# mippe_32u4.net
KiCad netlist of a schematic drawn in EAGLE
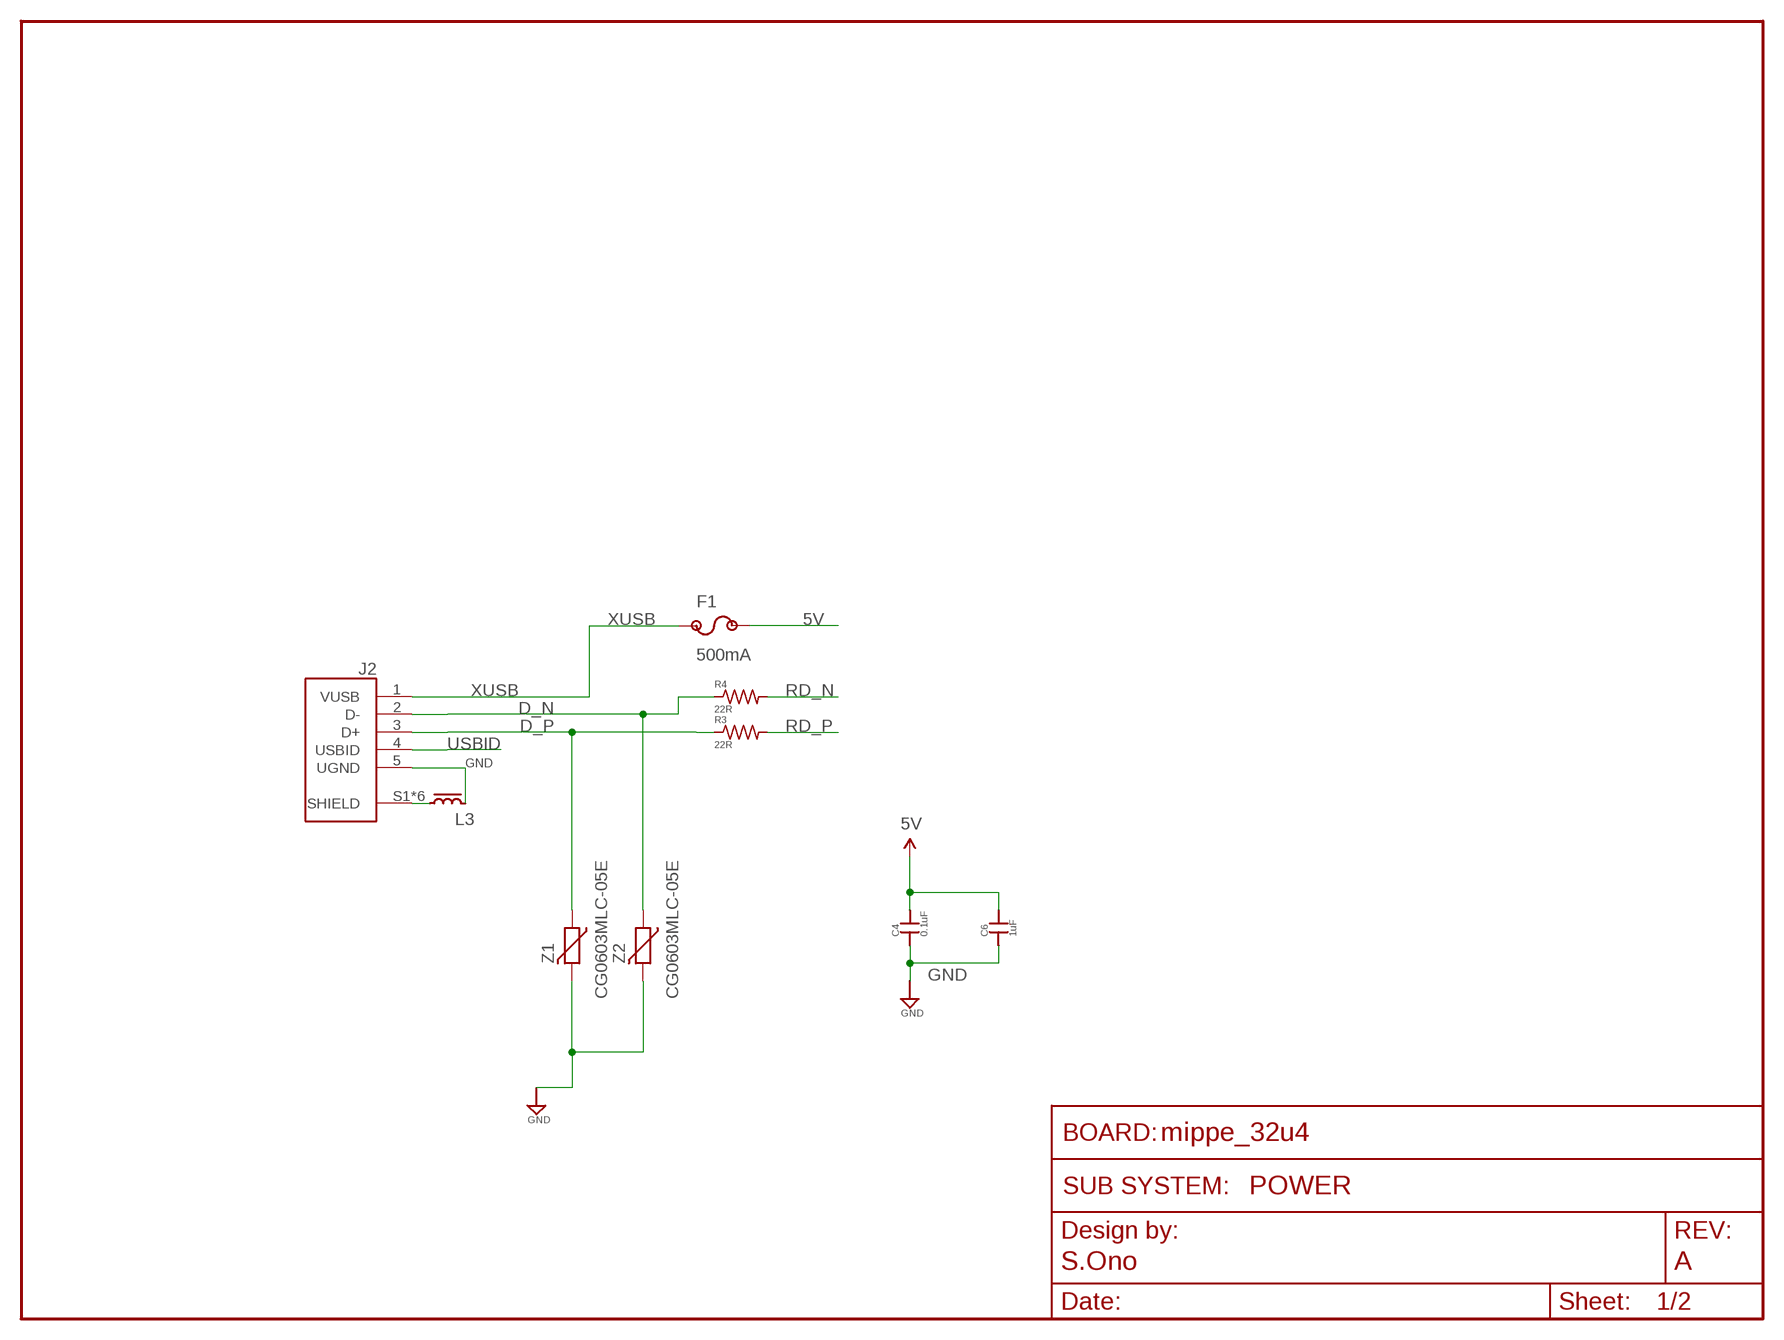
[diagram p0: schematic, sheet 1]
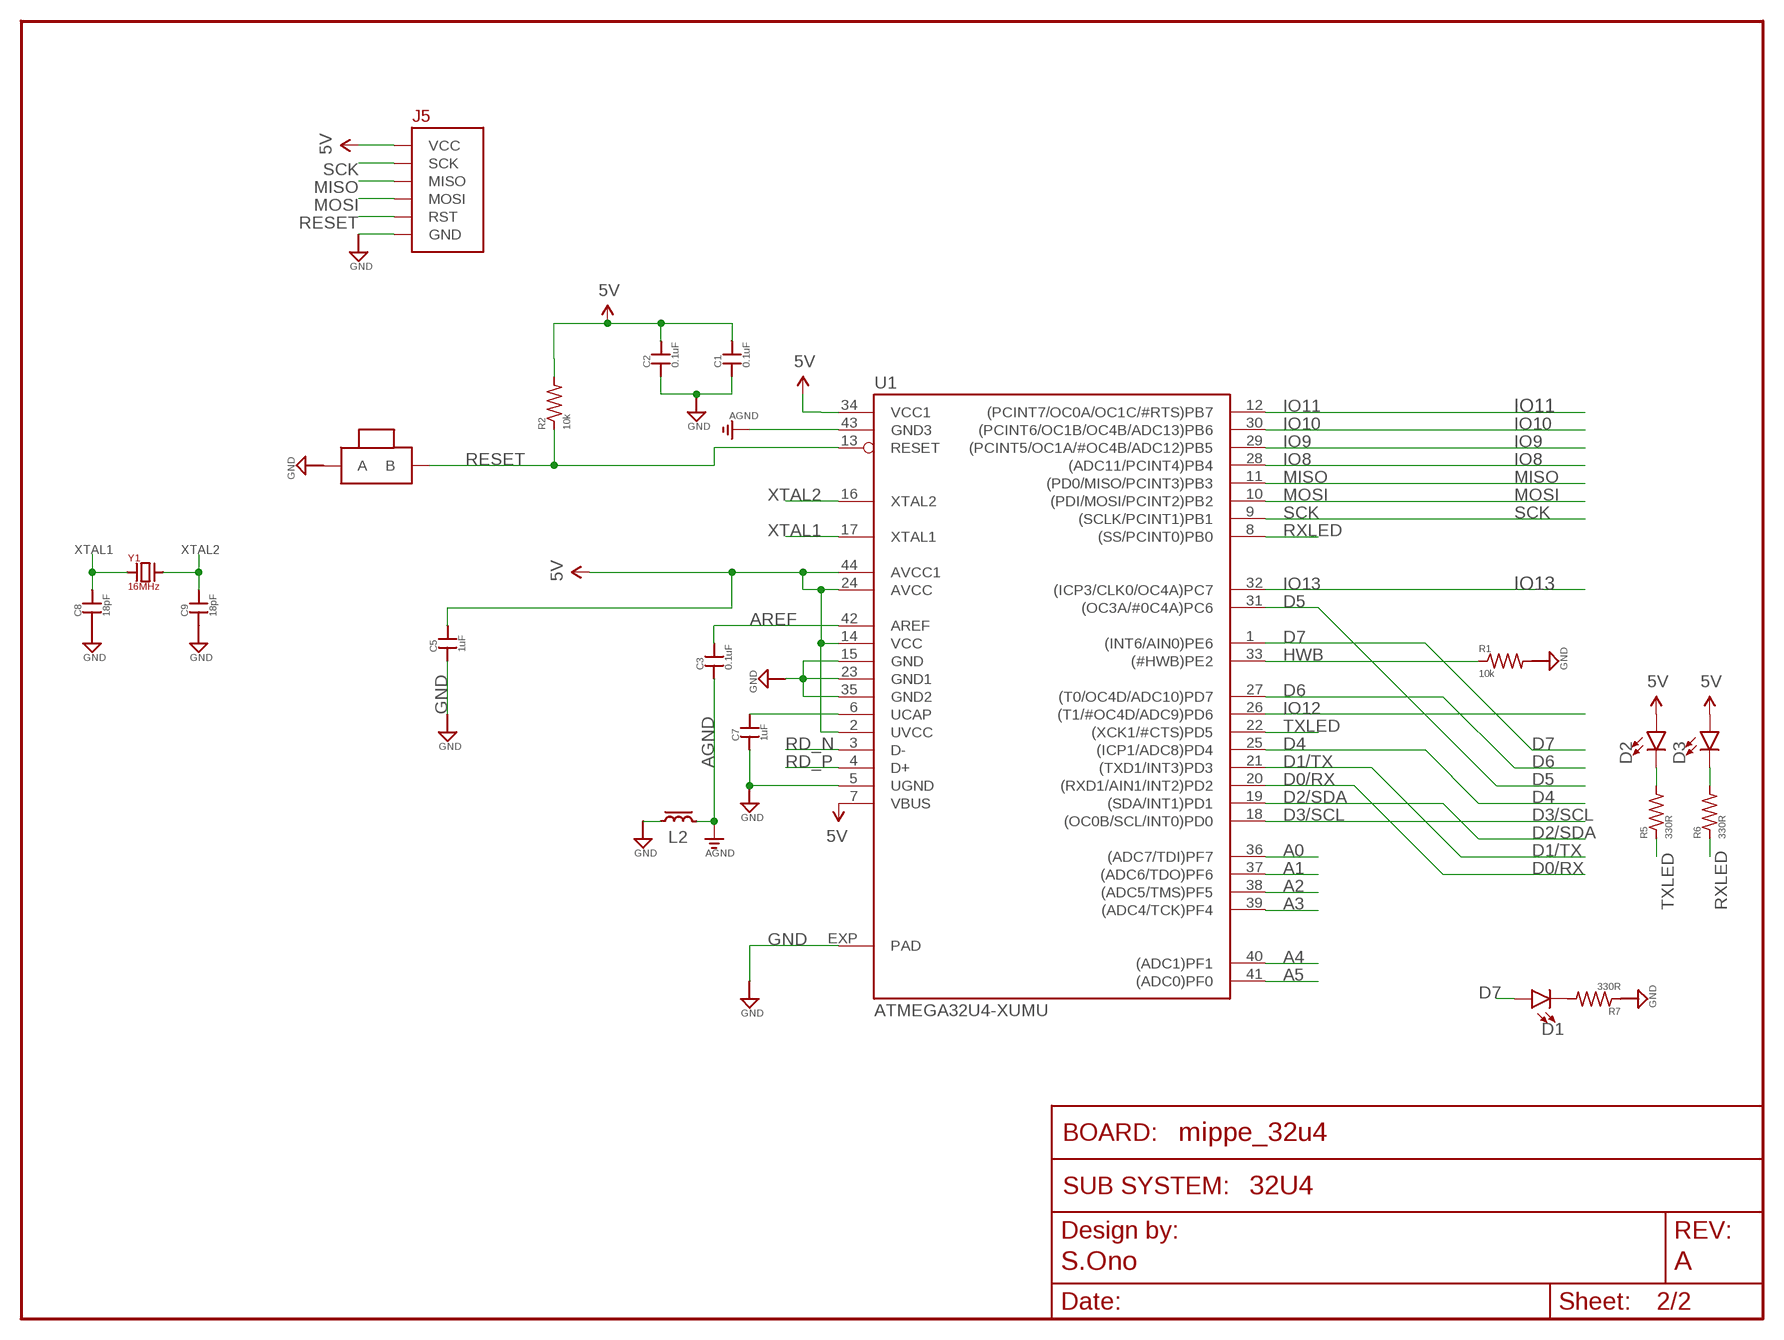
[diagram p1: schematic, sheet 2]

(export (version "E")
  (design (tool "Eeschema 10.0.6"))
  (components
    (comp (ref "C1")
      (value "0.1uF")
      (footprint "eagle-import:0402-CAP")
      (libsource (lib "eagle-import") (part "CAP0402-CAP"))
    )
    (comp (ref "C2")
      (value "0.1uF")
      (footprint "eagle-import:0402-CAP")
      (libsource (lib "eagle-import") (part "CAP0402-CAP"))
    )
    (comp (ref "C3")
      (value "0.1uF")
      (footprint "eagle-import:0402-CAP")
      (libsource (lib "eagle-import") (part "CAP0402-CAP"))
    )
    (comp (ref "C5")
      (value "1uF")
      (footprint "eagle-import:0402-CAP")
      (libsource (lib "eagle-import") (part "CAP0402-CAP"))
    )
    (comp (ref "C7")
      (value "1uF")
      (footprint "eagle-import:0402-CAP")
      (libsource (lib "eagle-import") (part "CAP0402-CAP"))
    )
    (comp (ref "C8")
      (value "18pF")
      (footprint "eagle-import:0402-CAP")
      (libsource (lib "eagle-import") (part "CAP0402-CAP"))
    )
    (comp (ref "C9")
      (value "18pF")
      (footprint "eagle-import:0402-CAP")
      (libsource (lib "eagle-import") (part "CAP0402-CAP"))
    )
    (comp (ref "D1")
      (value "LED0603")
      (footprint "eagle-import:LED-0603")
      (libsource (lib "eagle-import") (part "LED0603"))
    )
    (comp (ref "D2")
      (value "LED0603")
      (footprint "eagle-import:LED-0603")
      (libsource (lib "eagle-import") (part "LED0603"))
    )
    (comp (ref "D3")
      (value "LED0603")
      (footprint "eagle-import:LED-0603")
      (libsource (lib "eagle-import") (part "LED0603"))
    )
    (comp (ref "J5")
      (value "BURNIN")
      (footprint "eagle-import:BURNIN")
      (libsource (lib "eagle-import") (part "BURNIN"))
    )
    (comp (ref "L2")
      (value "IND")
      (footprint "eagle-import:IND_2012")
      (fields (field (name "MANUFACTURER_PART_NUMBER") "MLZ2012M1R0HT000"))
      (libsource (lib "eagle-import") (part "IND"))
    )
    (comp (ref "R1")
      (value "10k")
      (footprint "eagle-import:R0402")
      (libsource (lib "eagle-import") (part "R-US_R0402"))
    )
    (comp (ref "R2")
      (value "10k")
      (footprint "eagle-import:R0402")
      (libsource (lib "eagle-import") (part "R-US_R0402"))
    )
    (comp (ref "R5")
      (value "330R")
      (footprint "eagle-import:R0402")
      (libsource (lib "eagle-import") (part "R-US_R0402"))
    )
    (comp (ref "R6")
      (value "330R")
      (footprint "eagle-import:R0402")
      (libsource (lib "eagle-import") (part "R-US_R0402"))
    )
    (comp (ref "R7")
      (value "330R")
      (footprint "eagle-import:R0402")
      (libsource (lib "eagle-import") (part "R-US_R0402"))
    )
    (comp (ref "SW1")
      (value "BTN-PTS810")
      (footprint "eagle-import:BTN_PTS810")
      (libsource (lib "eagle-import") (part "BTN-PTS810"))
    )
    (comp (ref "U1")
      (value "ATMEGA32U4-XUMU")
      (footprint "eagle-import:QFN44ML7X7")
      (libsource (lib "eagle-import") (part "ATMEGA32U4-XUMU"))
    )
    (comp (ref "Y1")
      (value "16MHz")
      (footprint "eagle-import:XTAL500X320X130N")
      (libsource (lib "eagle-import") (part "CRYSTAL_SMOL"))
    )
    (comp (ref "C4")
      (value "0.1uF")
      (footprint "eagle-import:0402-CAP")
      (libsource (lib "eagle-import") (part "CAP0402-CAP"))
    )
    (comp (ref "C6")
      (value "1uF")
      (footprint "eagle-import:0402-CAP")
      (libsource (lib "eagle-import") (part "CAP0402-CAP"))
    )
    (comp (ref "F1")
      (value "500mA")
      (footprint "eagle-import:1206")
      (libsource (lib "eagle-import") (part "0ZCJ0050FF2G1206"))
    )
    (comp (ref "J2")
      (value "USB")
      (footprint "eagle-import:FCI_10103594-0001LF")
      (fields
        (field (name "DIGI-KEY_PART_NUMBER") "609-4050-1-ND")
        (field (name "MF") "Amphenol ICC")
        (field (name "MP") "10103594-0001LF")
      )
      (libsource (lib "eagle-import") (part "USB"))
    )
    (comp (ref "L3")
      (value "IND")
      (footprint "eagle-import:IND_2012")
      (fields (field (name "MANUFACTURER_PART_NUMBER") "MLZ2012M1R0HT000"))
      (libsource (lib "eagle-import") (part "IND"))
    )
    (comp (ref "R3")
      (value "22R")
      (footprint "eagle-import:R0402")
      (libsource (lib "eagle-import") (part "R-US_R0402"))
    )
    (comp (ref "R4")
      (value "22R")
      (footprint "eagle-import:R0402")
      (libsource (lib "eagle-import") (part "R-US_R0402"))
    )
    (comp (ref "Z1")
      (value "CG0603MLC-05E")
      (footprint "eagle-import:0603-RES")
      (libsource (lib "eagle-import") (part "VARISTOR"))
    )
    (comp (ref "Z2")
      (value "CG0603MLC-05E")
      (footprint "eagle-import:0603-RES")
      (libsource (lib "eagle-import") (part "VARISTOR"))
    )
  )
  (nets
    (net (code "1") (name "5V") (class "Default")
      (node (ref "C1") (pin "2") (pinfunction "2_2") (pintype "passive"))
      (node (ref "C2") (pin "2") (pinfunction "2_2") (pintype "passive"))
      (node (ref "C4") (pin "2") (pinfunction "2_2") (pintype "passive"))
      (node (ref "C5") (pin "2") (pinfunction "2_2") (pintype "passive"))
      (node (ref "C6") (pin "2") (pinfunction "2_2") (pintype "passive"))
      (node (ref "D2") (pin "A") (pinfunction "A_A") (pintype "passive"))
      (node (ref "D3") (pin "A") (pinfunction "A_A") (pintype "passive"))
      (node (ref "F1") (pin "2") (pinfunction "2_2") (pintype "passive"))
      (node (ref "J5") (pin "3.3V") (pinfunction "VCC_3.3V") (pintype "power_in"))
      (node (ref "R2") (pin "2") (pinfunction "2_2") (pintype "passive"))
      (node (ref "U1") (pin "14") (pinfunction "VCC_14") (pintype "power_in"))
      (node (ref "U1") (pin "2") (pinfunction "UVCC_2") (pintype "power_in"))
      (node (ref "U1") (pin "24") (pinfunction "AVCC_24") (pintype "power_in"))
      (node (ref "U1") (pin "34") (pinfunction "VCC1_34") (pintype "power_in"))
      (node (ref "U1") (pin "44") (pinfunction "AVCC1_44") (pintype "power_in"))
      (node (ref "U1") (pin "7") (pinfunction "VBUS_7") (pintype "input"))
    )
    (net (code "2") (name "A0") (class "Default")
      (node (ref "U1") (pin "36") (pinfunction "(ADC7/TDI)PF7_36") (pintype "bidirectional"))
    )
    (net (code "3") (name "A1") (class "Default")
      (node (ref "U1") (pin "37") (pinfunction "(ADC6/TDO)PF6_37") (pintype "bidirectional"))
    )
    (net (code "4") (name "A2") (class "Default")
      (node (ref "U1") (pin "38") (pinfunction "(ADC5/TMS)PF5_38") (pintype "bidirectional"))
    )
    (net (code "5") (name "A3") (class "Default")
      (node (ref "U1") (pin "39") (pinfunction "(ADC4/TCK)PF4_39") (pintype "bidirectional"))
    )
    (net (code "6") (name "A4") (class "Default")
      (node (ref "U1") (pin "40") (pinfunction "(ADC1)PF1_40") (pintype "bidirectional"))
    )
    (net (code "7") (name "A5") (class "Default")
      (node (ref "U1") (pin "41") (pinfunction "(ADC0)PF0_41") (pintype "bidirectional"))
    )
    (net (code "8") (name "AGND") (class "Default")
      (node (ref "C3") (pin "1") (pinfunction "1_1") (pintype "passive"))
      (node (ref "L2") (pin "2") (pinfunction "P$2_2") (pintype "passive"))
      (node (ref "U1") (pin "43") (pinfunction "GND3_43") (pintype "power_in"))
    )
    (net (code "9") (name "AREF") (class "Default")
      (node (ref "C3") (pin "2") (pinfunction "2_2") (pintype "passive"))
      (node (ref "U1") (pin "42") (pinfunction "AREF_42") (pintype "power_in"))
    )
    (net (code "10") (name "D0{slash}RX") (class "Default")
      (node (ref "U1") (pin "20") (pinfunction "(RXD1/AIN1/INT2)PD2_20") (pintype "bidirectional"))
    )
    (net (code "11") (name "D1{slash}TX") (class "Default")
      (node (ref "U1") (pin "21") (pinfunction "(TXD1/INT3)PD3_21") (pintype "bidirectional"))
    )
    (net (code "12") (name "D2{slash}SDA") (class "Default")
      (node (ref "U1") (pin "19") (pinfunction "(SDA/INT1)PD1_19") (pintype "bidirectional"))
    )
    (net (code "13") (name "D3{slash}SCL") (class "Default")
      (node (ref "U1") (pin "18") (pinfunction "(OC0B/SCL/INT0)PD0_18") (pintype "bidirectional"))
    )
    (net (code "14") (name "D4") (class "Default")
      (node (ref "U1") (pin "25") (pinfunction "(ICP1/ADC8)PD4_25") (pintype "bidirectional"))
    )
    (net (code "15") (name "D5") (class "Default")
      (node (ref "U1") (pin "31") (pinfunction "(OC3A/#0C4A)PC6_31") (pintype "bidirectional"))
    )
    (net (code "16") (name "D6") (class "Default")
      (node (ref "U1") (pin "27") (pinfunction "(T0/OC4D/ADC10)PD7_27") (pintype "bidirectional"))
    )
    (net (code "17") (name "D7") (class "Default")
      (node (ref "D1") (pin "A") (pinfunction "A_A") (pintype "passive"))
      (node (ref "U1") (pin "1") (pinfunction "(INT6/AIN0)PE6_1") (pintype "bidirectional"))
    )
    (net (code "18") (name "D_N") (class "Default")
      (node (ref "J2") (pin "2") (pinfunction "D-_2") (pintype "passive"))
      (node (ref "R4") (pin "1") (pinfunction "1_1") (pintype "passive"))
      (node (ref "Z2") (pin "1") (pinfunction "1_1") (pintype "passive"))
    )
    (net (code "19") (name "D_P") (class "Default")
      (node (ref "J2") (pin "3") (pinfunction "D+_3") (pintype "passive"))
      (node (ref "R3") (pin "1") (pinfunction "1_1") (pintype "passive"))
      (node (ref "Z1") (pin "1") (pinfunction "1_1") (pintype "passive"))
    )
    (net (code "20") (name "GND") (class "Default")
      (node (ref "C1") (pin "1") (pinfunction "1_1") (pintype "passive"))
      (node (ref "C2") (pin "1") (pinfunction "1_1") (pintype "passive"))
      (node (ref "C4") (pin "1") (pinfunction "1_1") (pintype "passive"))
      (node (ref "C5") (pin "1") (pinfunction "1_1") (pintype "passive"))
      (node (ref "C6") (pin "1") (pinfunction "1_1") (pintype "passive"))
      (node (ref "C7") (pin "1") (pinfunction "1_1") (pintype "passive"))
      (node (ref "C8") (pin "1") (pinfunction "1_1") (pintype "passive"))
      (node (ref "C9") (pin "1") (pinfunction "1_1") (pintype "passive"))
      (node (ref "J2") (pin "5") (pinfunction "UGND_5") (pintype "passive"))
      (node (ref "J5") (pin "GND") (pinfunction "GND_GND") (pintype "power_in"))
      (node (ref "L2") (pin "1") (pinfunction "P$1_1") (pintype "passive"))
      (node (ref "L3") (pin "2") (pinfunction "P$2_2") (pintype "passive"))
      (node (ref "R1") (pin "2") (pinfunction "2_2") (pintype "passive"))
      (node (ref "R7") (pin "1") (pinfunction "1_1") (pintype "passive"))
      (node (ref "SW1") (pin "1") (pinfunction "A_1") (pintype "bidirectional"))
      (node (ref "SW1") (pin "2") (pinfunction "A_2") (pintype "bidirectional"))
      (node (ref "U1") (pin "15") (pinfunction "GND_15") (pintype "power_in"))
      (node (ref "U1") (pin "23") (pinfunction "GND1_23") (pintype "power_in"))
      (node (ref "U1") (pin "35") (pinfunction "GND2_35") (pintype "power_in"))
      (node (ref "U1") (pin "5") (pinfunction "UGND_5") (pintype "power_in"))
      (node (ref "U1") (pin "EXP") (pinfunction "PAD_EXP") (pintype "power_in"))
      (node (ref "Z1") (pin "2") (pinfunction "2_2") (pintype "passive"))
      (node (ref "Z2") (pin "2") (pinfunction "2_2") (pintype "passive"))
    )
    (net (code "21") (name "HWB") (class "Default")
      (node (ref "R1") (pin "1") (pinfunction "1_1") (pintype "passive"))
      (node (ref "U1") (pin "33") (pinfunction "(#HWB)PE2_33") (pintype "bidirectional"))
    )
    (net (code "22") (name "IO8") (class "Default")
      (node (ref "U1") (pin "28") (pinfunction "(ADC11/PCINT4)PB4_28") (pintype "bidirectional"))
    )
    (net (code "23") (name "IO9") (class "Default")
      (node (ref "U1") (pin "29") (pinfunction "(PCINT5/OC1A/#OC4B/ADC12)PB5_29") (pintype "bidirectional"))
    )
    (net (code "24") (name "IO10") (class "Default")
      (node (ref "U1") (pin "30") (pinfunction "(PCINT6/OC1B/OC4B/ADC13)PB6_30") (pintype "bidirectional"))
    )
    (net (code "25") (name "IO11") (class "Default")
      (node (ref "U1") (pin "12") (pinfunction "(PCINT7/OC0A/OC1C/#RTS)PB7_12") (pintype "bidirectional"))
    )
    (net (code "26") (name "IO12") (class "Default")
      (node (ref "U1") (pin "26") (pinfunction "(T1/#OC4D/ADC9)PD6_26") (pintype "bidirectional"))
    )
    (net (code "27") (name "IO13") (class "Default")
      (node (ref "U1") (pin "32") (pinfunction "(ICP3/CLK0/OC4A)PC7_32") (pintype "bidirectional"))
    )
    (net (code "28") (name "MISO") (class "Default")
      (node (ref "J5") (pin "MISO") (pinfunction "MISO_MISO") (pintype "bidirectional"))
      (node (ref "U1") (pin "11") (pinfunction "(PD0/MISO/PCINT3)PB3_11") (pintype "bidirectional"))
    )
    (net (code "29") (name "MOSI") (class "Default")
      (node (ref "J5") (pin "MOSI") (pinfunction "MOSI_MOSI") (pintype "bidirectional"))
      (node (ref "U1") (pin "10") (pinfunction "(PDI/MOSI/PCINT2)PB2_10") (pintype "bidirectional"))
    )
    (net (code "30") (name "Net-(D1-PadC)") (class "Default")
      (node (ref "D1") (pin "C") (pinfunction "C_C") (pintype "passive"))
      (node (ref "R7") (pin "2") (pinfunction "2_2") (pintype "passive"))
    )
    (net (code "31") (name "Net-(D2-PadC)") (class "Default")
      (node (ref "D2") (pin "C") (pinfunction "C_C") (pintype "passive"))
      (node (ref "R5") (pin "2") (pinfunction "2_2") (pintype "passive"))
    )
    (net (code "32") (name "Net-(D3-PadC)") (class "Default")
      (node (ref "D3") (pin "C") (pinfunction "C_C") (pintype "passive"))
      (node (ref "R6") (pin "2") (pinfunction "2_2") (pintype "passive"))
    )
    (net (code "33") (name "Net-(L3-P$1)") (class "Default")
      (node (ref "J2") (pin "S1") (pinfunction "SHIELD_S1") (pintype "passive"))
      (node (ref "J2") (pin "S2") (pinfunction "SHIELD_S2") (pintype "passive"))
      (node (ref "J2") (pin "S3") (pinfunction "SHIELD_S3") (pintype "passive"))
      (node (ref "J2") (pin "S4") (pinfunction "SHIELD_S4") (pintype "passive"))
      (node (ref "J2") (pin "S5") (pinfunction "SHIELD_S5") (pintype "passive"))
      (node (ref "J2") (pin "S6") (pinfunction "SHIELD_S6") (pintype "passive"))
      (node (ref "L3") (pin "1") (pinfunction "P$1_1") (pintype "passive"))
    )
    (net (code "34") (name "Net-(U1-UCAP)") (class "Default")
      (node (ref "C7") (pin "2") (pinfunction "2_2") (pintype "passive"))
      (node (ref "U1") (pin "6") (pinfunction "UCAP_6") (pintype "passive"))
    )
    (net (code "35") (name "RD_N") (class "Default")
      (node (ref "R4") (pin "2") (pinfunction "2_2") (pintype "passive"))
      (node (ref "U1") (pin "3") (pinfunction "D-_3") (pintype "bidirectional"))
    )
    (net (code "36") (name "RD_P") (class "Default")
      (node (ref "R3") (pin "2") (pinfunction "2_2") (pintype "passive"))
      (node (ref "U1") (pin "4") (pinfunction "D+_4") (pintype "bidirectional"))
    )
    (net (code "37") (name "RESET") (class "Default")
      (node (ref "J5") (pin "RST") (pinfunction "RST_RST") (pintype "bidirectional"))
      (node (ref "R2") (pin "1") (pinfunction "1_1") (pintype "passive"))
      (node (ref "SW1") (pin "3") (pinfunction "B_3") (pintype "bidirectional"))
      (node (ref "SW1") (pin "4") (pinfunction "B_4") (pintype "bidirectional"))
      (node (ref "U1") (pin "13") (pinfunction "RESET_13") (pintype "input"))
    )
    (net (code "38") (name "RXLED") (class "Default")
      (node (ref "R6") (pin "1") (pinfunction "1_1") (pintype "passive"))
      (node (ref "U1") (pin "8") (pinfunction "(SS/PCINT0)PB0_8") (pintype "bidirectional"))
    )
    (net (code "39") (name "SCK") (class "Default")
      (node (ref "J5") (pin "SCK") (pinfunction "SCK_SCK") (pintype "bidirectional"))
      (node (ref "U1") (pin "9") (pinfunction "(SCLK/PCINT1)PB1_9") (pintype "bidirectional"))
    )
    (net (code "40") (name "TXLED") (class "Default")
      (node (ref "R5") (pin "1") (pinfunction "1_1") (pintype "passive"))
      (node (ref "U1") (pin "22") (pinfunction "(XCK1/#CTS)PD5_22") (pintype "bidirectional"))
    )
    (net (code "41") (name "USBID") (class "Default")
      (node (ref "J2") (pin "4") (pinfunction "USBID_4") (pintype "passive"))
    )
    (net (code "42") (name "XTAL1") (class "Default")
      (node (ref "C8") (pin "2") (pinfunction "2_2") (pintype "passive"))
      (node (ref "U1") (pin "17") (pinfunction "XTAL1_17") (pintype "bidirectional"))
      (node (ref "Y1") (pin "1") (pinfunction "A_1") (pintype "passive"))
    )
    (net (code "43") (name "XTAL2") (class "Default")
      (node (ref "C9") (pin "2") (pinfunction "2_2") (pintype "passive"))
      (node (ref "U1") (pin "16") (pinfunction "XTAL2_16") (pintype "bidirectional"))
      (node (ref "Y1") (pin "2") (pinfunction "B_2") (pintype "passive"))
    )
    (net (code "44") (name "XUSB") (class "Default")
      (node (ref "F1") (pin "1") (pinfunction "1_1") (pintype "passive"))
      (node (ref "J2") (pin "1") (pinfunction "VUSB_1") (pintype "passive"))
    )
  )
)
